# xyzxyz.net
KiCad netlist of a schematic drawn in EAGLE
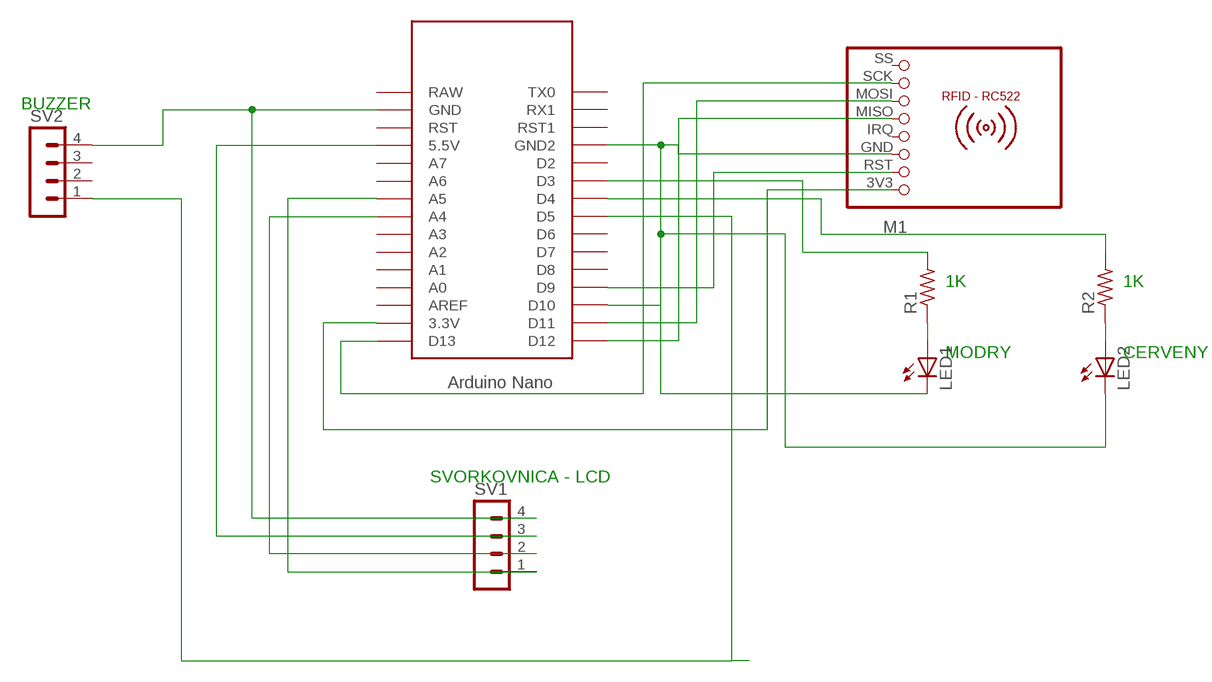
[diagram p0: schematic, sheet 1]

(export (version "E")
  (design (tool "Eeschema 10.0.6"))
  (components
    (comp (ref "LED1")
      (value "LED3MM")
      (footprint "eagle-import:LED3MM")
      (libsource (lib "eagle-import") (part "LED3MM"))
    )
    (comp (ref "LED2")
      (value "LED3MM")
      (footprint "eagle-import:LED3MM")
      (libsource (lib "eagle-import") (part "LED3MM"))
    )
    (comp (ref "M1")
      (value "RFID-RC522")
      (footprint "eagle-import:RFID-RC522")
      (libsource (lib "eagle-import") (part "RFID-RC522"))
    )
    (comp (ref "R1")
      (value "R-US_0414/15")
      (footprint "eagle-import:0414_15")
      (libsource (lib "eagle-import") (part "R-US_0414/15"))
    )
    (comp (ref "R2")
      (value "R-US_0414/15")
      (footprint "eagle-import:0414_15")
      (libsource (lib "eagle-import") (part "R-US_0414/15"))
    )
    (comp (ref "SV1")
      (value "MA04-1")
      (footprint "eagle-import:MA04-1")
      (libsource (lib "eagle-import") (part "MA04-1"))
    )
    (comp (ref "SV2")
      (value "MA04-1")
      (footprint "eagle-import:MA04-1")
      (libsource (lib "eagle-import") (part "MA04-1"))
    )
    (comp (ref "U$1")
      (value "NANO")
      (footprint "eagle-import:NANO")
      (libsource (lib "eagle-import") (part "NANO"))
    )
  )
  (nets
    (net (code "1") (name "Net-(LED1-C)") (class "Default")
      (node (ref "LED1") (pin "K") (pinfunction "C_K") (pintype "passive"))
      (node (ref "LED2") (pin "K") (pinfunction "C_K") (pintype "passive"))
      (node (ref "M1") (pin "GND") (pinfunction "3_GND") (pintype "passive"))
      (node (ref "U$1") (pin "GND1") (pinfunction "GND2_GND1") (pintype "bidirectional"))
    )
    (net (code "2") (name "Net-(LED1-PadA)") (class "Default")
      (node (ref "LED1") (pin "A") (pinfunction "A_A") (pintype "passive"))
      (node (ref "R1") (pin "1") (pinfunction "1_1") (pintype "passive"))
    )
    (net (code "3") (name "Net-(LED2-PadA)") (class "Default")
      (node (ref "LED2") (pin "A") (pinfunction "A_A") (pintype "passive"))
      (node (ref "R2") (pin "1") (pinfunction "1_1") (pintype "passive"))
    )
    (net (code "4") (name "Net-(M1-1)") (class "Default")
      (node (ref "M1") (pin "3V3") (pinfunction "1_3V3") (pintype "passive"))
      (node (ref "U$1") (pin "3.3V") (pinfunction "3.3V_3.3V") (pintype "bidirectional"))
    )
    (net (code "5") (name "Net-(M1-2)") (class "Default")
      (node (ref "M1") (pin "RST") (pinfunction "2_RST") (pintype "passive"))
      (node (ref "U$1") (pin "D9") (pinfunction "D9_D9") (pintype "bidirectional"))
    )
    (net (code "6") (name "Net-(M1-5)") (class "Default")
      (node (ref "M1") (pin "MISO") (pinfunction "5_MISO") (pintype "passive"))
      (node (ref "U$1") (pin "D12") (pinfunction "D12_D12") (pintype "bidirectional"))
    )
    (net (code "7") (name "Net-(M1-6)") (class "Default")
      (node (ref "M1") (pin "MOSI") (pinfunction "6_MOSI") (pintype "passive"))
      (node (ref "U$1") (pin "D11") (pinfunction "D11_D11") (pintype "bidirectional"))
    )
    (net (code "8") (name "Net-(M1-7)") (class "Default")
      (node (ref "M1") (pin "SCK") (pinfunction "7_SCK") (pintype "passive"))
      (node (ref "U$1") (pin "D13") (pinfunction "D13_D13") (pintype "bidirectional"))
    )
    (net (code "9") (name "Net-(R1-Pad2)") (class "Default")
      (node (ref "R1") (pin "2") (pinfunction "2_2") (pintype "passive"))
      (node (ref "U$1") (pin "D3") (pinfunction "D3_D3") (pintype "bidirectional"))
    )
    (net (code "10") (name "Net-(R2-Pad2)") (class "Default")
      (node (ref "R2") (pin "2") (pinfunction "2_2") (pintype "passive"))
      (node (ref "U$1") (pin "D4") (pinfunction "D4_D4") (pintype "bidirectional"))
    )
    (net (code "11") (name "Net-(SV1-Pad1)") (class "Default")
      (node (ref "SV1") (pin "1") (pinfunction "1_1") (pintype "passive"))
      (node (ref "U$1") (pin "A5") (pinfunction "A5_A5") (pintype "bidirectional"))
    )
    (net (code "12") (name "Net-(SV1-Pad2)") (class "Default")
      (node (ref "SV1") (pin "2") (pinfunction "2_2") (pintype "passive"))
      (node (ref "U$1") (pin "A4") (pinfunction "A4_A4") (pintype "bidirectional"))
    )
    (net (code "13") (name "Net-(SV1-Pad4)") (class "Default")
      (node (ref "SV1") (pin "4") (pinfunction "4_4") (pintype "passive"))
      (node (ref "SV2") (pin "4") (pinfunction "4_4") (pintype "passive"))
      (node (ref "U$1") (pin "GND") (pinfunction "GND_GND") (pintype "bidirectional"))
    )
    (net (code "14") (name "Net-(SV2-Pad1)") (class "Default")
      (node (ref "SV2") (pin "1") (pinfunction "1_1") (pintype "passive"))
      (node (ref "U$1") (pin "D5") (pinfunction "D5_D5") (pintype "bidirectional"))
    )
    (net (code "15") (name "Net-(U$1-5.5V)") (class "Default")
      (node (ref "SV1") (pin "3") (pinfunction "3_3") (pintype "passive"))
      (node (ref "U$1") (pin "5V") (pinfunction "5.5V_5V") (pintype "bidirectional"))
    )
    (net (code "16") (name "unconnected-(M1-4-PadIRQ)") (class "Default")
      (node (ref "M1") (pin "IRQ") (pinfunction "4_IRQ") (pintype "passive"))
    )
    (net (code "17") (name "unconnected-(M1-8-PadSS)") (class "Default")
      (node (ref "M1") (pin "SS") (pinfunction "8_SS") (pintype "passive"))
    )
    (net (code "18") (name "unconnected-(SV2-Pad2)") (class "Default")
      (node (ref "SV2") (pin "2") (pinfunction "2_2") (pintype "passive"))
    )
    (net (code "19") (name "unconnected-(SV2-Pad3)") (class "Default")
      (node (ref "SV2") (pin "3") (pinfunction "3_3") (pintype "passive"))
    )
    (net (code "20") (name "unconnected-(U$1-PadA0)") (class "Default")
      (node (ref "U$1") (pin "A0") (pinfunction "A0_A0") (pintype "bidirectional"))
    )
    (net (code "21") (name "unconnected-(U$1-PadA1)") (class "Default")
      (node (ref "U$1") (pin "A1") (pinfunction "A1_A1") (pintype "bidirectional"))
    )
    (net (code "22") (name "unconnected-(U$1-PadA2)") (class "Default")
      (node (ref "U$1") (pin "A2") (pinfunction "A2_A2") (pintype "bidirectional"))
    )
    (net (code "23") (name "unconnected-(U$1-PadA3)") (class "Default")
      (node (ref "U$1") (pin "A3") (pinfunction "A3_A3") (pintype "bidirectional"))
    )
    (net (code "24") (name "unconnected-(U$1-PadA6)") (class "Default")
      (node (ref "U$1") (pin "A6") (pinfunction "A6_A6") (pintype "bidirectional"))
    )
    (net (code "25") (name "unconnected-(U$1-PadA7)") (class "Default")
      (node (ref "U$1") (pin "A7") (pinfunction "A7_A7") (pintype "bidirectional"))
    )
    (net (code "26") (name "unconnected-(U$1-PadAREF)") (class "Default")
      (node (ref "U$1") (pin "AREF") (pinfunction "AREF_AREF") (pintype "bidirectional"))
    )
    (net (code "27") (name "unconnected-(U$1-PadD2)") (class "Default")
      (node (ref "U$1") (pin "D2") (pinfunction "D2_D2") (pintype "bidirectional"))
    )
    (net (code "28") (name "unconnected-(U$1-PadD6)") (class "Default")
      (node (ref "U$1") (pin "D6") (pinfunction "D6_D6") (pintype "bidirectional"))
    )
    (net (code "29") (name "unconnected-(U$1-PadD7)") (class "Default")
      (node (ref "U$1") (pin "D7") (pinfunction "D7_D7") (pintype "bidirectional"))
    )
    (net (code "30") (name "unconnected-(U$1-PadD8)") (class "Default")
      (node (ref "U$1") (pin "D8") (pinfunction "D8_D8") (pintype "bidirectional"))
    )
    (net (code "31") (name "unconnected-(U$1-PadD10)") (class "Default")
      (node (ref "U$1") (pin "D10") (pinfunction "D10_D10") (pintype "bidirectional"))
    )
    (net (code "32") (name "unconnected-(U$1-PadICSP1)") (class "Default")
      (node (ref "U$1") (pin "ICSP1") (pinfunction "ICSP1_ICSP1") (pintype "bidirectional"))
    )
    (net (code "33") (name "unconnected-(U$1-PadICSP2)") (class "Default")
      (node (ref "U$1") (pin "ICSP2") (pinfunction "ICSP2_ICSP2") (pintype "bidirectional"))
    )
    (net (code "34") (name "unconnected-(U$1-PadICSP3)") (class "Default")
      (node (ref "U$1") (pin "ICSP3") (pinfunction "ICSP3_ICSP3") (pintype "bidirectional"))
    )
    (net (code "35") (name "unconnected-(U$1-PadICSP4)") (class "Default")
      (node (ref "U$1") (pin "ICSP4") (pinfunction "ICSP4_ICSP4") (pintype "bidirectional"))
    )
    (net (code "36") (name "unconnected-(U$1-PadICSP5)") (class "Default")
      (node (ref "U$1") (pin "ICSP5") (pinfunction "ICSP5_ICSP5") (pintype "bidirectional"))
    )
    (net (code "37") (name "unconnected-(U$1-PadICSP6)") (class "Default")
      (node (ref "U$1") (pin "ICSP6") (pinfunction "ICSP6_ICSP6") (pintype "bidirectional"))
    )
    (net (code "38") (name "unconnected-(U$1-PadRAW)") (class "Default")
      (node (ref "U$1") (pin "RAW") (pinfunction "RAW_RAW") (pintype "bidirectional"))
    )
    (net (code "39") (name "unconnected-(U$1-PadRST)") (class "Default")
      (node (ref "U$1") (pin "RST") (pinfunction "RST_RST") (pintype "bidirectional"))
    )
    (net (code "40") (name "unconnected-(U$1-PadRST1)") (class "Default")
      (node (ref "U$1") (pin "RST1") (pinfunction "RST1_RST1") (pintype "bidirectional"))
    )
    (net (code "41") (name "unconnected-(U$1-PadRX1)") (class "Default")
      (node (ref "U$1") (pin "RX1") (pinfunction "RX1_RX1") (pintype "bidirectional"))
    )
    (net (code "42") (name "unconnected-(U$1-PadTX0)") (class "Default")
      (node (ref "U$1") (pin "TX0") (pinfunction "TX0_TX0") (pintype "bidirectional"))
    )
  )
)
